# SYSTEM_PMIC_RK805.net
KiCad netlist of a schematic drawn in Altium Designer
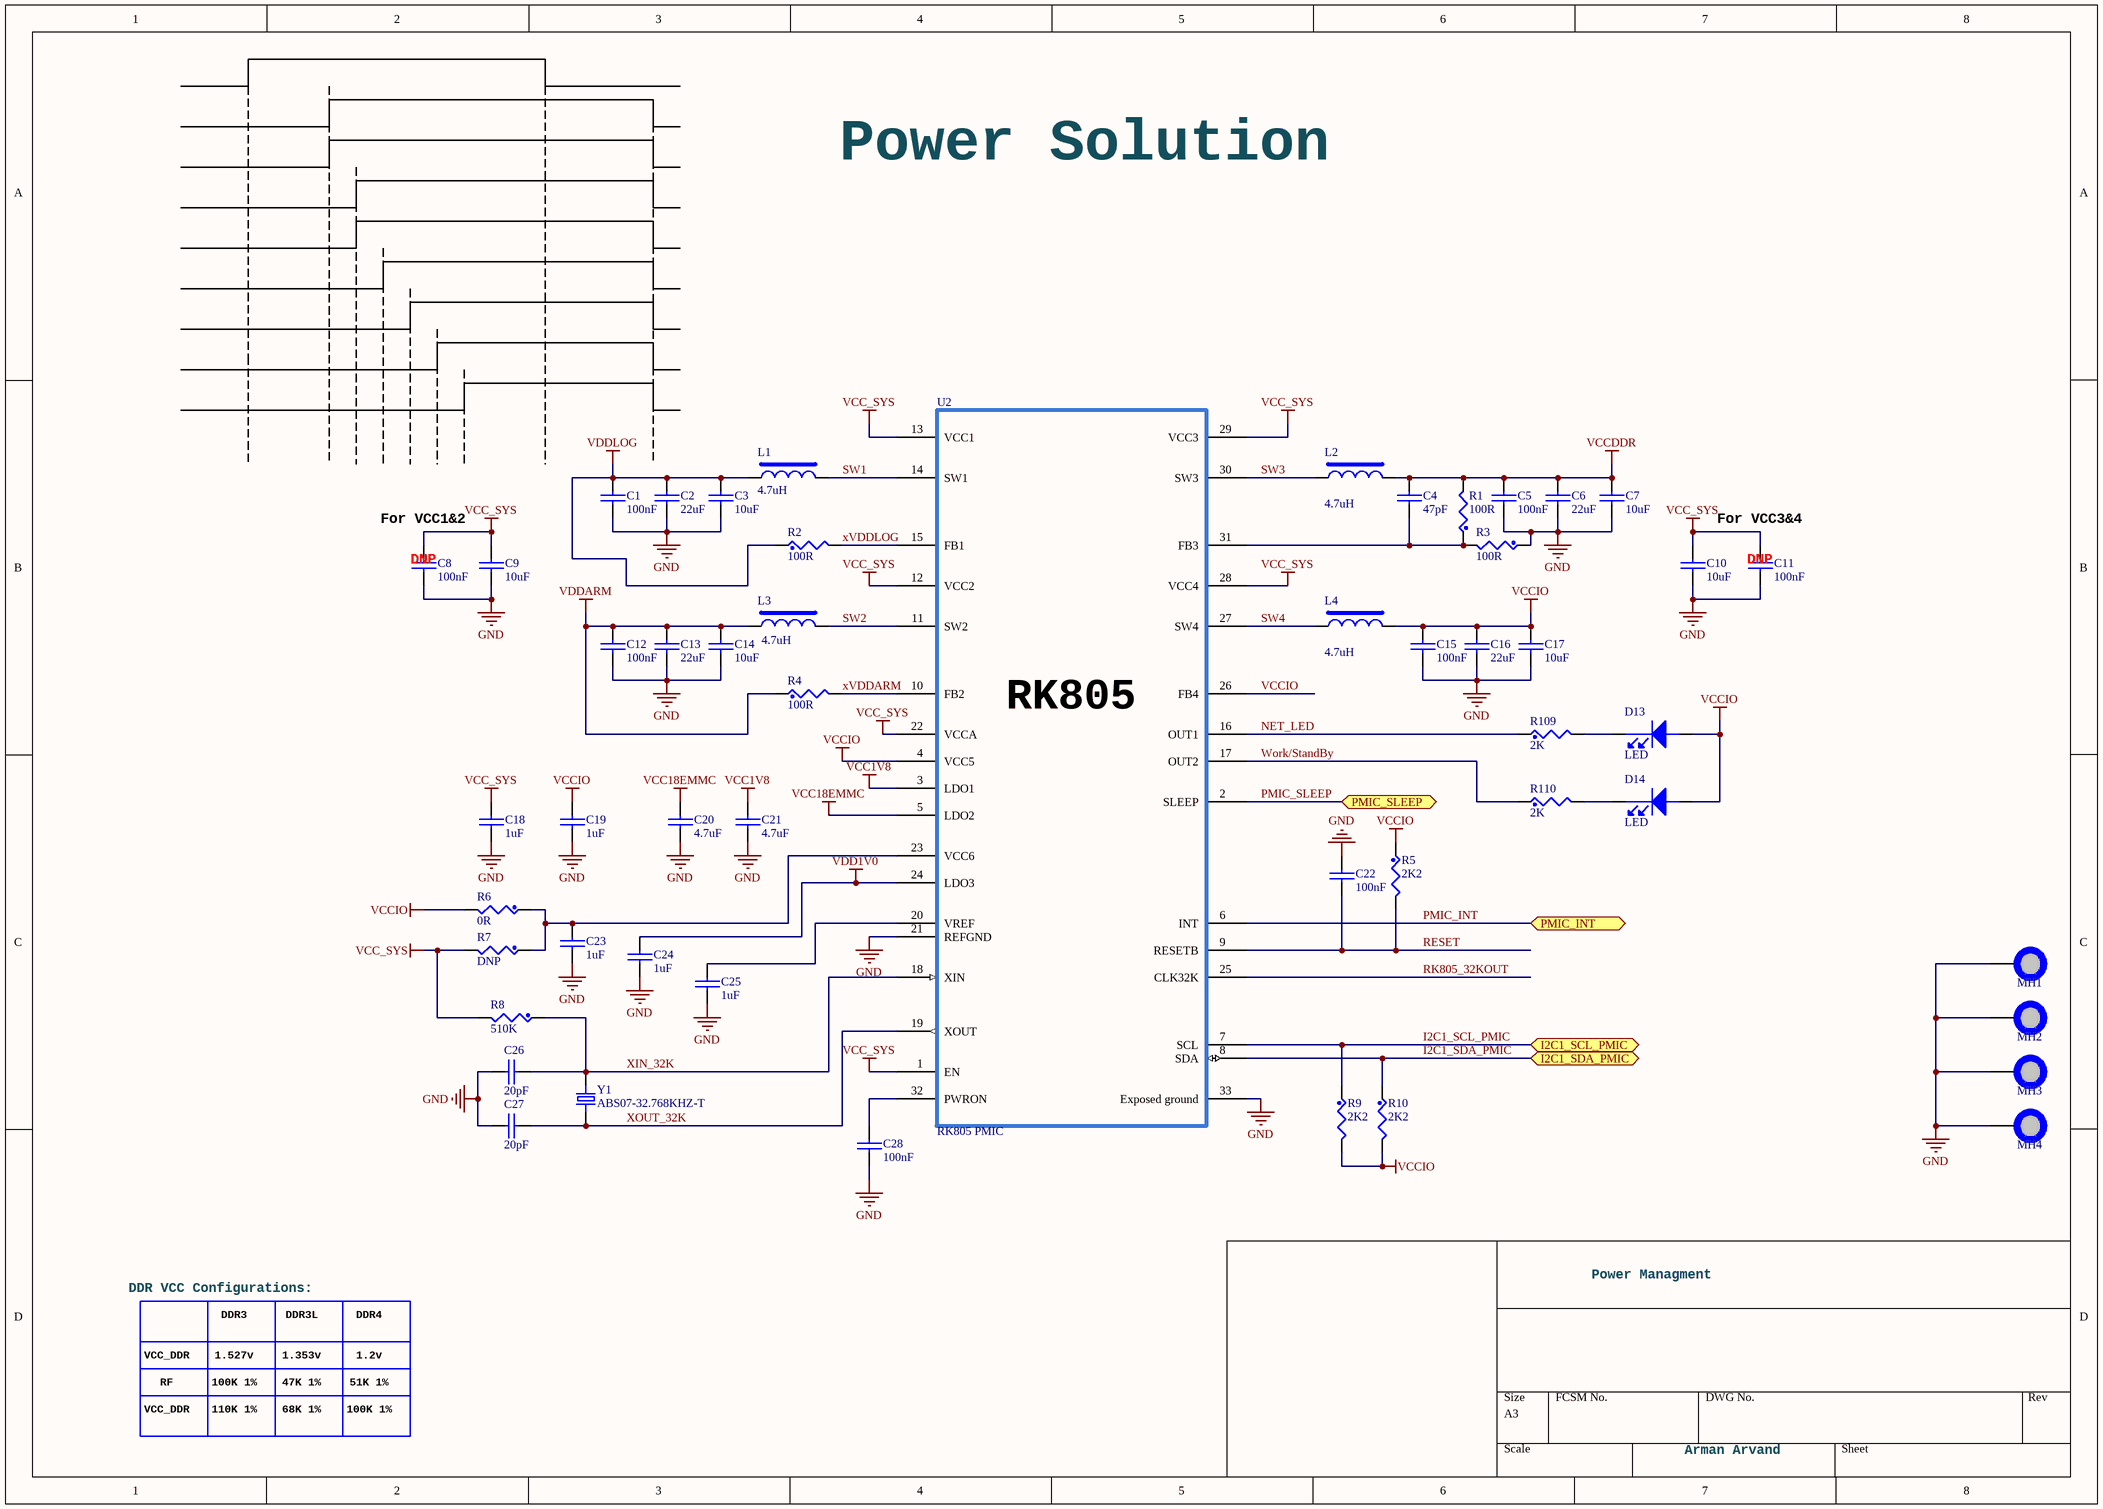
[diagram p0: SYSTEM_PMIC_RK805.SchDoc]

(export (version "E")
  (design (tool "Eeschema 10.0.6"))
  (components
    (comp (ref "C1")
      (value "100nF")
      (footprint "0402_CC - C")
      (libsource (lib "AAR_RockChip_RK3328") (part "CAP_NP"))
    )
    (comp (ref "C2")
      (value "22uF")
      (footprint "0603_CC")
      (libsource (lib "AAR_RockChip_RK3328") (part "CAP_NP"))
    )
    (comp (ref "C3")
      (value "10uF")
      (footprint "0603_CC")
      (libsource (lib "AAR_RockChip_RK3328") (part "CAP_NP"))
    )
    (comp (ref "C4")
      (value "47pF")
      (footprint "0402_CC - C")
      (libsource (lib "AAR_RockChip_RK3328") (part "CAP_NP"))
    )
    (comp (ref "C5")
      (value "100nF")
      (footprint "0402_CC - C")
      (libsource (lib "AAR_RockChip_RK3328") (part "CAP_NP"))
    )
    (comp (ref "C6")
      (value "22uF")
      (footprint "0603_CC")
      (libsource (lib "AAR_RockChip_RK3328") (part "CAP_NP"))
    )
    (comp (ref "C7")
      (value "10uF")
      (footprint "0603_CC")
      (libsource (lib "AAR_RockChip_RK3328") (part "CAP_NP"))
    )
    (comp (ref "C8")
      (value "100nF")
      (footprint "0402_CC - C")
      (libsource (lib "AAR_RockChip_RK3328") (part "CAP_NP"))
    )
    (comp (ref "C9")
      (value "10uF")
      (footprint "0805_CC")
      (libsource (lib "AAR_RockChip_RK3328") (part "CAP_NP"))
    )
    (comp (ref "C10")
      (value "10uF")
      (footprint "0805_CC")
      (libsource (lib "AAR_RockChip_RK3328") (part "CAP_NP"))
    )
    (comp (ref "C11")
      (value "100nF")
      (footprint "0402_CC - C")
      (libsource (lib "AAR_RockChip_RK3328") (part "CAP_NP"))
    )
    (comp (ref "C12")
      (value "100nF")
      (footprint "0402_CC - C")
      (libsource (lib "AAR_RockChip_RK3328") (part "CAP_NP"))
    )
    (comp (ref "C13")
      (value "22uF")
      (footprint "0603_CC")
      (libsource (lib "AAR_RockChip_RK3328") (part "CAP_NP"))
    )
    (comp (ref "C14")
      (value "10uF")
      (footprint "0603_CC")
      (libsource (lib "AAR_RockChip_RK3328") (part "CAP_NP"))
    )
    (comp (ref "C15")
      (value "100nF")
      (footprint "0402_CC - C")
      (libsource (lib "AAR_RockChip_RK3328") (part "CAP_NP"))
    )
    (comp (ref "C16")
      (value "22uF")
      (footprint "0603_CC")
      (libsource (lib "AAR_RockChip_RK3328") (part "CAP_NP"))
    )
    (comp (ref "C17")
      (value "10uF")
      (footprint "0603_CC")
      (libsource (lib "AAR_RockChip_RK3328") (part "CAP_NP"))
    )
    (comp (ref "C18")
      (value "1uF")
      (footprint "0402_CC - C")
      (libsource (lib "AAR_RockChip_RK3328") (part "CAP_NP"))
    )
    (comp (ref "C19")
      (value "1uF")
      (footprint "0402_CC - C")
      (libsource (lib "AAR_RockChip_RK3328") (part "CAP_NP"))
    )
    (comp (ref "C20")
      (value "4.7uF")
      (footprint "0603_CC")
      (libsource (lib "AAR_RockChip_RK3328") (part "CAP_NP"))
    )
    (comp (ref "C21")
      (value "4.7uF")
      (footprint "0603_CC")
      (libsource (lib "AAR_RockChip_RK3328") (part "CAP_NP"))
    )
    (comp (ref "C22")
      (value "100nF")
      (footprint "0402_CC - C")
      (libsource (lib "AAR_RockChip_RK3328") (part "CAP_NP"))
    )
    (comp (ref "C23")
      (value "1uF")
      (footprint "0402_CC - C")
      (libsource (lib "AAR_RockChip_RK3328") (part "CAP_NP"))
    )
    (comp (ref "C24")
      (value "1uF")
      (footprint "0402_CC - C")
      (libsource (lib "AAR_RockChip_RK3328") (part "CAP_NP"))
    )
    (comp (ref "C25")
      (value "1uF")
      (footprint "0402_CC - C")
      (libsource (lib "AAR_RockChip_RK3328") (part "CAP_NP"))
    )
    (comp (ref "C26")
      (value "20pF")
      (footprint "0402_CC - C")
      (libsource (lib "AAR_RockChip_RK3328") (part "CAP_NP"))
    )
    (comp (ref "C27")
      (value "20pF")
      (footprint "0402_CC - C")
      (libsource (lib "AAR_RockChip_RK3328") (part "CAP_NP"))
    )
    (comp (ref "C28")
      (value "100nF")
      (footprint "0402_CC - C")
      (libsource (lib "AAR_RockChip_RK3328") (part "CAP_NP"))
    )
    (comp (ref "D13")
      (value "LED")
      (footprint "LED_0603")
      (libsource (lib "AAR_RockChip_RK3328") (part "LED"))
    )
    (comp (ref "D14")
      (value "LED")
      (footprint "LED_0603")
      (libsource (lib "AAR_RockChip_RK3328") (part "LED"))
    )
    (comp (ref "L1")
      (value "4.7uH")
      (footprint "INDC3020X12N")
      (description "Fixed Inductors 4.7uH 20% 200mOhm 1.9A, From TDK, \r\nLis: AAR")
      (fields (field (name "MFR_PART_NO") "TMS252012ALM-4R7MTAA") (field (name "MFR") "TDK"))
      (libsource (lib "AAR_RockChip_RK3328") (part "TMS252012ALM-4R7MTAA"))
    )
    (comp (ref "L2")
      (value "4.7uH")
      (footprint "INDC3020X12N")
      (description "Fixed Inductors 4.7uH 20% 200mOhm 1.9A, From TDK, \r\nLis: AAR")
      (fields (field (name "MFR_PART_NO") "TMS252012ALM-4R7MTAA") (field (name "MFR") "TDK"))
      (libsource (lib "AAR_RockChip_RK3328") (part "TMS252012ALM-4R7MTAA"))
    )
    (comp (ref "L3")
      (value "4.7uH")
      (footprint "INDC3020X12N")
      (description "Fixed Inductors 4.7uH 20% 200mOhm 1.9A, From TDK, \r\nLis: AAR")
      (fields (field (name "MFR_PART_NO") "TMS252012ALM-4R7MTAA") (field (name "MFR") "TDK"))
      (libsource (lib "AAR_RockChip_RK3328") (part "TMS252012ALM-4R7MTAA"))
    )
    (comp (ref "L4")
      (value "4.7uH")
      (footprint "INDC3020X12N")
      (description "Fixed Inductors 4.7uH 20% 200mOhm 1.9A, From TDK, \r\nLis: AAR")
      (fields (field (name "MFR_PART_NO") "TMS252012ALM-4R7MTAA") (field (name "MFR") "TDK"))
      (libsource (lib "AAR_RockChip_RK3328") (part "TMS252012ALM-4R7MTAA"))
    )
    (comp (ref "MH1")
      (value "MH_5MMC_2.2MMD")
      (footprint "MH_5MMD_2.2MMD")
      (description "Mounting Hole 5mm Diameter, 2.2mm Drill")
      (libsource (lib "iMX6 Rex_V1I1") (part "MH_5MMC_2.2MMD"))
    )
    (comp (ref "MH2")
      (value "MH_5MMC_2.2MMD")
      (footprint "MH_5MMD_2.2MMD")
      (description "Mounting Hole 5mm Diameter, 2.2mm Drill")
      (libsource (lib "iMX6 Rex_V1I1") (part "MH_5MMC_2.2MMD"))
    )
    (comp (ref "MH3")
      (value "MH_5MMC_2.2MMD")
      (footprint "MH_5MMD_2.2MMD")
      (description "Mounting Hole 5mm Diameter, 2.2mm Drill")
      (libsource (lib "iMX6 Rex_V1I1") (part "MH_5MMC_2.2MMD"))
    )
    (comp (ref "MH4")
      (value "MH_5MMC_2.2MMD")
      (footprint "MH_5MMD_2.2MMD")
      (description "Mounting Hole 5mm Diameter, 2.2mm Drill")
      (libsource (lib "iMX6 Rex_V1I1") (part "MH_5MMC_2.2MMD"))
    )
    (comp (ref "R1")
      (value "100R")
      (footprint "0402_CR")
      (libsource (lib "AAR_RockChip_RK3328") (part "RES"))
    )
    (comp (ref "R2")
      (value "100R")
      (footprint "0402_CR")
      (libsource (lib "AAR_RockChip_RK3328") (part "RES"))
    )
    (comp (ref "R3")
      (value "100R")
      (footprint "0402_CR")
      (libsource (lib "AAR_RockChip_RK3328") (part "RES"))
    )
    (comp (ref "R4")
      (value "100R")
      (footprint "0402_CR")
      (libsource (lib "AAR_RockChip_RK3328") (part "RES"))
    )
    (comp (ref "R5") (value "2K2") (footprint "0402_CR") (libsource (lib "AAR_RockChip_RK3328") (part "RES")))
    (comp (ref "R6") (value "0R") (footprint "0402_CR") (libsource (lib "AAR_RockChip_RK3328") (part "RES")))
    (comp (ref "R7") (value "DNP") (footprint "0402_CR") (libsource (lib "AAR_RockChip_RK3328") (part "RES")))
    (comp (ref "R8")
      (value "510K")
      (footprint "0402_CR")
      (libsource (lib "AAR_RockChip_RK3328") (part "RES"))
    )
    (comp (ref "R9") (value "2K2") (footprint "0402_CR") (libsource (lib "AAR_RockChip_RK3328") (part "RES")))
    (comp (ref "R10")
      (value "2K2")
      (footprint "0402_CR")
      (libsource (lib "AAR_RockChip_RK3328") (part "RES"))
    )
    (comp (ref "R109")
      (value "2K")
      (footprint "0402_CR")
      (libsource (lib "AAR_RockChip_RK3328") (part "RES"))
    )
    (comp (ref "R110")
      (value "2K")
      (footprint "0402_CR")
      (libsource (lib "AAR_RockChip_RK3328") (part "RES"))
    )
    (comp (ref "U2")
      (value "RK805 PMIC")
      (footprint "QFN40P400X400X80_HS-33N")
      (description "RK805 PMIC, AAR")
      (libsource (lib "AAR_RockChip_RK3328") (part "RK805"))
    )
    (comp (ref "Y1")
      (value "ABS07-32.768KHZ-T")
      (footprint "XTAL_ABS07-32.768KHZ-T")
      (description "32.768kHz Â±20ppm Crystal 12.5pF 70 kOhms 2-SMD, No Lead")
      (fields (field (name "MFR") "Abracon LLC") (field (name "MFR_PART_NO") "ABS07-32.768KHZ-4-T"))
      (libsource (lib "AAR_RockChip_RK3328") (part "ABS07-32.768KHZ-T"))
    )
  )
  (nets
    (net (code "1") (name "/I2C1_SCL_PMIC") (class "Default")
      (node (ref "R9") (pin "1") (pinfunction "1_1") (pintype "passive"))
      (node (ref "U2") (pin "7") (pinfunction "SCL_7") (pintype "tri_state"))
    )
    (net (code "2") (name "/I2C1_SDA_PMIC") (class "Default")
      (node (ref "R10") (pin "1") (pinfunction "1_1") (pintype "passive"))
      (node (ref "U2") (pin "8") (pinfunction "SDA_8") (pintype "bidirectional"))
    )
    (net (code "3") (name "/NET_LED") (class "Default")
      (node (ref "R109") (pin "1") (pinfunction "1_1") (pintype "passive"))
      (node (ref "U2") (pin "16") (pinfunction "OUT1_16") (pintype "power_in"))
    )
    (net (code "4") (name "/PMIC_INT") (class "Default")
      (node (ref "U2") (pin "6") (pinfunction "INT_6") (pintype "open_collector"))
    )
    (net (code "5") (name "/PMIC_SLEEP") (class "Default")
      (node (ref "U2") (pin "2") (pinfunction "SLEEP_2") (pintype "passive"))
    )
    (net (code "6") (name "/RESET") (class "Default")
      (node (ref "C22") (pin "1") (pinfunction "1_1") (pintype "passive"))
      (node (ref "R5") (pin "2") (pinfunction "2_2") (pintype "passive"))
      (node (ref "U2") (pin "9") (pinfunction "RESETB_9") (pintype "open_collector"))
    )
    (net (code "7") (name "/RK805_32KOUT") (class "Default")
      (node (ref "U2") (pin "25") (pinfunction "CLK32K_25") (pintype "open_collector"))
    )
    (net (code "8") (name "/SW1") (class "Default")
      (node (ref "L1") (pin "2") (pinfunction "2_2") (pintype "passive"))
      (node (ref "U2") (pin "14") (pinfunction "SW1_14") (pintype "power_in"))
    )
    (net (code "9") (name "/SW2") (class "Default")
      (node (ref "L3") (pin "2") (pinfunction "2_2") (pintype "passive"))
      (node (ref "U2") (pin "11") (pinfunction "SW2_11") (pintype "power_in"))
    )
    (net (code "10") (name "/SW3") (class "Default")
      (node (ref "L2") (pin "1") (pinfunction "1_1") (pintype "passive"))
      (node (ref "U2") (pin "30") (pinfunction "SW3_30") (pintype "power_in"))
    )
    (net (code "11") (name "/SW4") (class "Default")
      (node (ref "L4") (pin "1") (pinfunction "1_1") (pintype "passive"))
      (node (ref "U2") (pin "27") (pinfunction "SW4_27") (pintype "power_in"))
    )
    (net (code "12") (name "/Work{slash}StandBy") (class "Default")
      (node (ref "R110") (pin "1") (pinfunction "1_1") (pintype "passive"))
      (node (ref "U2") (pin "17") (pinfunction "OUT2_17") (pintype "power_in"))
    )
    (net (code "13") (name "/XIN_32K") (class "Default")
      (node (ref "C26") (pin "2") (pinfunction "2_2") (pintype "passive"))
      (node (ref "R8") (pin "1") (pinfunction "1_1") (pintype "passive"))
      (node (ref "U2") (pin "18") (pinfunction "XIN_18") (pintype "input"))
      (node (ref "Y1") (pin "2") (pinfunction "2_2") (pintype "passive"))
    )
    (net (code "14") (name "/XOUT_32K") (class "Default")
      (node (ref "C27") (pin "2") (pinfunction "2_2") (pintype "passive"))
      (node (ref "U2") (pin "19") (pinfunction "XOUT_19") (pintype "output"))
      (node (ref "Y1") (pin "1") (pinfunction "1_1") (pintype "passive"))
    )
    (net (code "15") (name "/xVDDARM") (class "Default")
      (node (ref "R4") (pin "2") (pinfunction "2_2") (pintype "passive"))
      (node (ref "U2") (pin "10") (pinfunction "FB2_10") (pintype "power_in"))
    )
    (net (code "16") (name "/xVDDLOG") (class "Default")
      (node (ref "R2") (pin "2") (pinfunction "2_2") (pintype "passive"))
      (node (ref "U2") (pin "15") (pinfunction "FB1_15") (pintype "power_in"))
    )
    (net (code "17") (name "GND") (class "Default")
      (node (ref "C1") (pin "2") (pinfunction "2_2") (pintype "passive"))
      (node (ref "C10") (pin "2") (pinfunction "2_2") (pintype "passive"))
      (node (ref "C11") (pin "2") (pinfunction "2_2") (pintype "passive"))
      (node (ref "C12") (pin "2") (pinfunction "2_2") (pintype "passive"))
      (node (ref "C13") (pin "2") (pinfunction "2_2") (pintype "passive"))
      (node (ref "C14") (pin "2") (pinfunction "2_2") (pintype "passive"))
      (node (ref "C15") (pin "2") (pinfunction "2_2") (pintype "passive"))
      (node (ref "C16") (pin "2") (pinfunction "2_2") (pintype "passive"))
      (node (ref "C17") (pin "2") (pinfunction "2_2") (pintype "passive"))
      (node (ref "C18") (pin "2") (pinfunction "2_2") (pintype "passive"))
      (node (ref "C19") (pin "2") (pinfunction "2_2") (pintype "passive"))
      (node (ref "C2") (pin "2") (pinfunction "2_2") (pintype "passive"))
      (node (ref "C20") (pin "2") (pinfunction "2_2") (pintype "passive"))
      (node (ref "C21") (pin "2") (pinfunction "2_2") (pintype "passive"))
      (node (ref "C22") (pin "2") (pinfunction "2_2") (pintype "passive"))
      (node (ref "C23") (pin "2") (pinfunction "2_2") (pintype "passive"))
      (node (ref "C24") (pin "2") (pinfunction "2_2") (pintype "passive"))
      (node (ref "C25") (pin "2") (pinfunction "2_2") (pintype "passive"))
      (node (ref "C26") (pin "1") (pinfunction "1_1") (pintype "passive"))
      (node (ref "C27") (pin "1") (pinfunction "1_1") (pintype "passive"))
      (node (ref "C28") (pin "1") (pinfunction "1_1") (pintype "passive"))
      (node (ref "C3") (pin "2") (pinfunction "2_2") (pintype "passive"))
      (node (ref "C5") (pin "2") (pinfunction "2_2") (pintype "passive"))
      (node (ref "C6") (pin "2") (pinfunction "2_2") (pintype "passive"))
      (node (ref "C7") (pin "2") (pinfunction "2_2") (pintype "passive"))
      (node (ref "C8") (pin "2") (pinfunction "2_2") (pintype "passive"))
      (node (ref "C9") (pin "2") (pinfunction "2_2") (pintype "passive"))
      (node (ref "MH1") (pin "1") (pinfunction "1_1") (pintype "passive"))
      (node (ref "MH2") (pin "1") (pinfunction "1_1") (pintype "passive"))
      (node (ref "MH3") (pin "1") (pinfunction "1_1") (pintype "passive"))
      (node (ref "MH4") (pin "1") (pinfunction "1_1") (pintype "passive"))
      (node (ref "R3") (pin "1") (pinfunction "1_1") (pintype "passive"))
      (node (ref "U2") (pin "21") (pinfunction "REFGND_21") (pintype "power_in"))
      (node (ref "U2") (pin "33") (pinfunction "Exposed_ground_33") (pintype "power_in"))
    )
    (net (code "18") (name "Net-(D13-CATHODE)") (class "Default")
      (node (ref "D13") (pin "C") (pinfunction "CATHODE_C") (pintype "passive"))
      (node (ref "R109") (pin "2") (pinfunction "2_2") (pintype "passive"))
    )
    (net (code "19") (name "Net-(D14-CATHODE)") (class "Default")
      (node (ref "D14") (pin "C") (pinfunction "CATHODE_C") (pintype "passive"))
      (node (ref "R110") (pin "2") (pinfunction "2_2") (pintype "passive"))
    )
    (net (code "20") (name "Net-(U2-FB3)") (class "Default")
      (node (ref "C4") (pin "2") (pinfunction "2_2") (pintype "passive"))
      (node (ref "R1") (pin "1") (pinfunction "1_1") (pintype "passive"))
      (node (ref "R3") (pin "2") (pinfunction "2_2") (pintype "passive"))
      (node (ref "U2") (pin "31") (pinfunction "FB3_31") (pintype "power_in"))
    )
    (net (code "21") (name "Net-(U2-PWRON)") (class "Default")
      (node (ref "C28") (pin "2") (pinfunction "2_2") (pintype "passive"))
      (node (ref "U2") (pin "32") (pinfunction "PWRON_32") (pintype "open_collector"))
    )
    (net (code "22") (name "Net-(U2-VCC6)") (class "Default")
      (node (ref "C23") (pin "1") (pinfunction "1_1") (pintype "passive"))
      (node (ref "R6") (pin "1") (pinfunction "1_1") (pintype "passive"))
      (node (ref "R7") (pin "1") (pinfunction "1_1") (pintype "passive"))
      (node (ref "U2") (pin "23") (pinfunction "VCC6_23") (pintype "power_in"))
    )
    (net (code "23") (name "Net-(U2-VREF)") (class "Default")
      (node (ref "C25") (pin "1") (pinfunction "1_1") (pintype "passive"))
      (node (ref "U2") (pin "20") (pinfunction "VREF_20") (pintype "power_in"))
    )
    (net (code "24") (name "VCC1V8") (class "Default")
      (node (ref "C21") (pin "1") (pinfunction "1_1") (pintype "passive"))
      (node (ref "U2") (pin "3") (pinfunction "LDO1_3") (pintype "power_in"))
    )
    (net (code "25") (name "VCC18EMMC") (class "Default")
      (node (ref "C20") (pin "1") (pinfunction "1_1") (pintype "passive"))
      (node (ref "U2") (pin "5") (pinfunction "LDO2_5") (pintype "power_in"))
    )
    (net (code "26") (name "VCCDDR") (class "Default")
      (node (ref "C4") (pin "1") (pinfunction "1_1") (pintype "passive"))
      (node (ref "C5") (pin "1") (pinfunction "1_1") (pintype "passive"))
      (node (ref "C6") (pin "1") (pinfunction "1_1") (pintype "passive"))
      (node (ref "C7") (pin "1") (pinfunction "1_1") (pintype "passive"))
      (node (ref "L2") (pin "2") (pinfunction "2_2") (pintype "passive"))
      (node (ref "R1") (pin "2") (pinfunction "2_2") (pintype "passive"))
    )
    (net (code "27") (name "VCCIO") (class "Default")
      (node (ref "C15") (pin "1") (pinfunction "1_1") (pintype "passive"))
      (node (ref "C16") (pin "1") (pinfunction "1_1") (pintype "passive"))
      (node (ref "C17") (pin "1") (pinfunction "1_1") (pintype "passive"))
      (node (ref "C19") (pin "1") (pinfunction "1_1") (pintype "passive"))
      (node (ref "D13") (pin "A") (pinfunction "ANODE_A") (pintype "passive"))
      (node (ref "D14") (pin "A") (pinfunction "ANODE_A") (pintype "passive"))
      (node (ref "L4") (pin "2") (pinfunction "2_2") (pintype "passive"))
      (node (ref "R10") (pin "2") (pinfunction "2_2") (pintype "passive"))
      (node (ref "R5") (pin "1") (pinfunction "1_1") (pintype "passive"))
      (node (ref "R6") (pin "2") (pinfunction "2_2") (pintype "passive"))
      (node (ref "R9") (pin "2") (pinfunction "2_2") (pintype "passive"))
      (node (ref "U2") (pin "26") (pinfunction "FB4_26") (pintype "power_in"))
      (node (ref "U2") (pin "4") (pinfunction "VCC5_4") (pintype "power_in"))
    )
    (net (code "28") (name "VCC_SYS") (class "Default")
      (node (ref "C10") (pin "1") (pinfunction "1_1") (pintype "passive"))
      (node (ref "C11") (pin "1") (pinfunction "1_1") (pintype "passive"))
      (node (ref "C18") (pin "1") (pinfunction "1_1") (pintype "passive"))
      (node (ref "C8") (pin "1") (pinfunction "1_1") (pintype "passive"))
      (node (ref "C9") (pin "1") (pinfunction "1_1") (pintype "passive"))
      (node (ref "R7") (pin "2") (pinfunction "2_2") (pintype "passive"))
      (node (ref "R8") (pin "2") (pinfunction "2_2") (pintype "passive"))
      (node (ref "U2") (pin "1") (pinfunction "EN_1") (pintype "open_collector"))
      (node (ref "U2") (pin "12") (pinfunction "VCC2_12") (pintype "power_in"))
      (node (ref "U2") (pin "13") (pinfunction "VCC1_13") (pintype "power_in"))
      (node (ref "U2") (pin "22") (pinfunction "VCCA_22") (pintype "power_in"))
      (node (ref "U2") (pin "28") (pinfunction "VCC4_28") (pintype "power_in"))
      (node (ref "U2") (pin "29") (pinfunction "VCC3_29") (pintype "power_in"))
    )
    (net (code "29") (name "VDD1V0") (class "Default")
      (node (ref "C24") (pin "1") (pinfunction "1_1") (pintype "passive"))
      (node (ref "U2") (pin "24") (pinfunction "LDO3_24") (pintype "power_in"))
    )
    (net (code "30") (name "VDDARM") (class "Default")
      (node (ref "C12") (pin "1") (pinfunction "1_1") (pintype "passive"))
      (node (ref "C13") (pin "1") (pinfunction "1_1") (pintype "passive"))
      (node (ref "C14") (pin "1") (pinfunction "1_1") (pintype "passive"))
      (node (ref "L3") (pin "1") (pinfunction "1_1") (pintype "passive"))
      (node (ref "R4") (pin "1") (pinfunction "1_1") (pintype "passive"))
    )
    (net (code "31") (name "VDDLOG") (class "Default")
      (node (ref "C1") (pin "1") (pinfunction "1_1") (pintype "passive"))
      (node (ref "C2") (pin "1") (pinfunction "1_1") (pintype "passive"))
      (node (ref "C3") (pin "1") (pinfunction "1_1") (pintype "passive"))
      (node (ref "L1") (pin "1") (pinfunction "1_1") (pintype "passive"))
      (node (ref "R2") (pin "1") (pinfunction "1_1") (pintype "passive"))
    )
  )
)
